# esquematico.net
KiCad netlist of a schematic drawn in Altium Designer
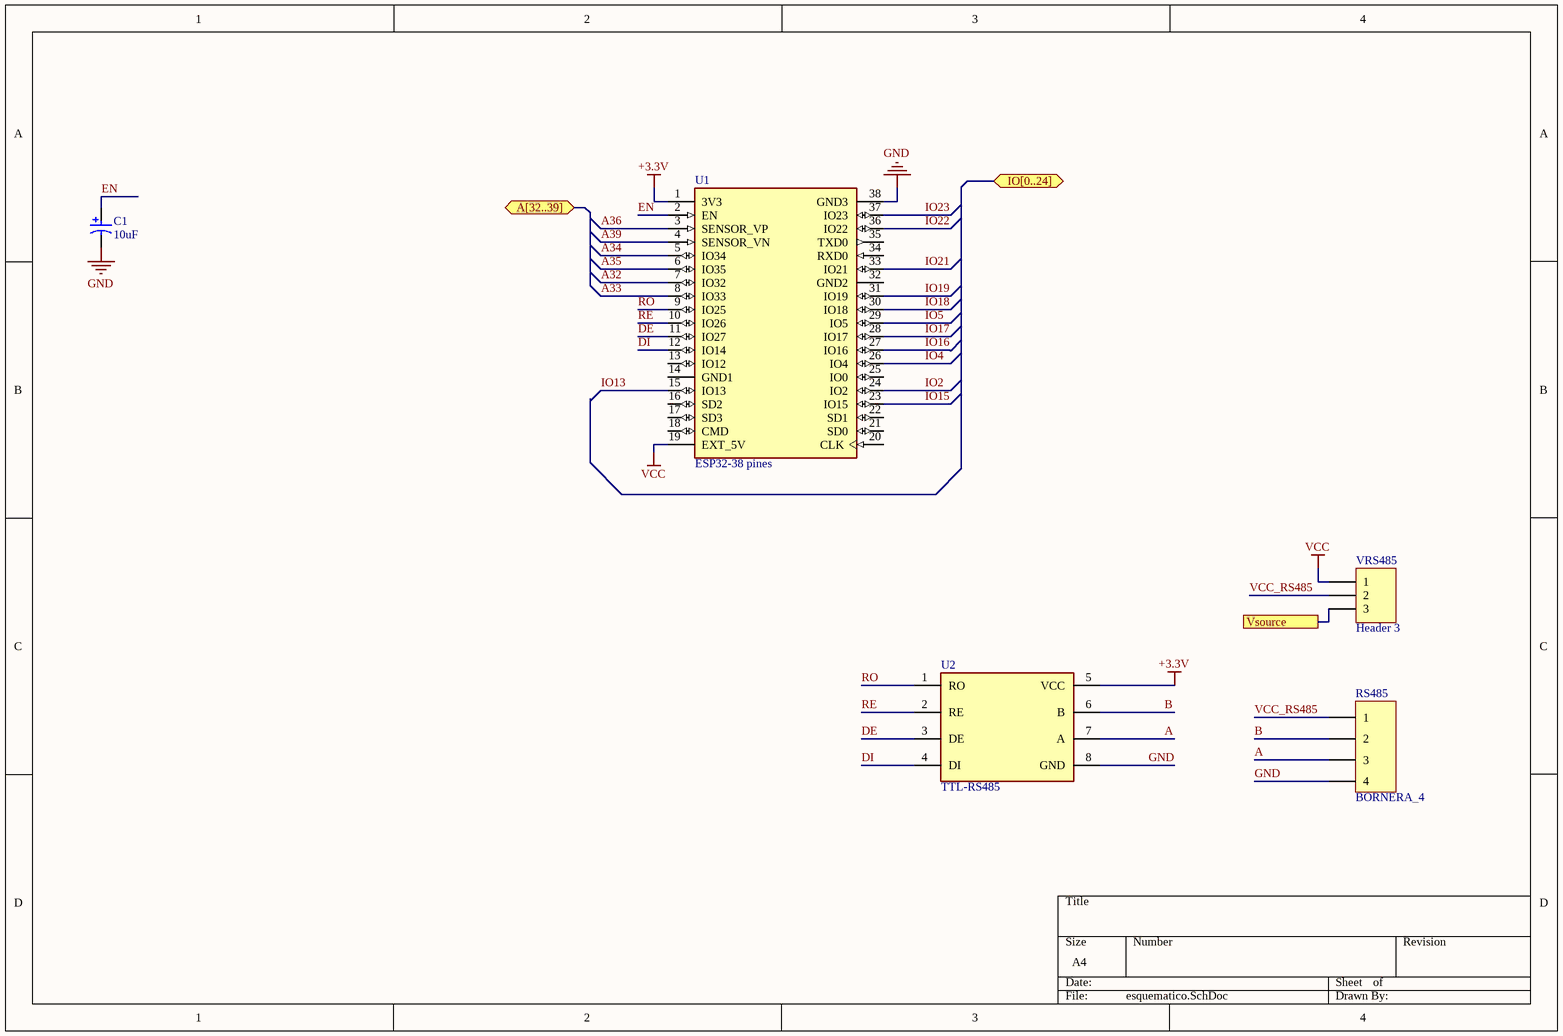
[diagram p0: esquematico.SchDoc]

(export (version "E")
  (design (tool "Eeschema 10.0.6"))
  (components
    (comp (ref "C1")
      (value "10uF")
      (footprint "FP-CAPACITOR")
      (libsource (lib "simbologia") (part "Electrolytic capacitor"))
    )
    (comp (ref "RS485")
      (value "BORNERA_4")
      (footprint "BORNERA_4")
      (libsource (lib "simbologia") (part "BORNERA_4"))
    )
    (comp (ref "U1")
      (value "ESP32-38 pines")
      (footprint "ESP32")
      (libsource (lib "simbologia") (part "ESP32-38 pines"))
    )
    (comp (ref "U2")
      (value "TTL-RS485")
      (footprint "TTL_RS485")
      (libsource (lib "simbologia") (part "TTL-RS485"))
    )
    (comp (ref "VRS485")
      (value "Header 3")
      (footprint "HDR1X3")
      (description "Header, 3-Pin")
      (fields (field (name "PUBLISHER") "Altium Limited"))
      (libsource (lib "Miscellaneous Connectors") (part "Header 3"))
    )
  )
  (nets
    (net (code "16") (name "+3.3V") (class "Default")
      (node (ref "U1") (pin "1") (pinfunction "3V3_1") (pintype "power_in"))
      (node (ref "U2") (pin "5") (pinfunction "VCC_5") (pintype "power_in"))
    )
    (net (code "17") (name "/A") (class "Default")
      (node (ref "RS485") (pin "3") (pinfunction "3_3") (pintype "passive"))
      (node (ref "U2") (pin "7") (pinfunction "A_7") (pintype "power_in"))
    )
    (net (code "18") (name "/A32") (class "Default")
      (node (ref "U1") (pin "7") (pinfunction "IO32_7") (pintype "bidirectional"))
    )
    (net (code "19") (name "/A33") (class "Default")
      (node (ref "U1") (pin "8") (pinfunction "IO33_8") (pintype "bidirectional"))
    )
    (net (code "20") (name "/A34") (class "Default")
      (node (ref "U1") (pin "5") (pinfunction "IO34_5") (pintype "bidirectional"))
    )
    (net (code "21") (name "/A35") (class "Default")
      (node (ref "U1") (pin "6") (pinfunction "IO35_6") (pintype "bidirectional"))
    )
    (net (code "22") (name "/A36") (class "Default")
      (node (ref "U1") (pin "3") (pinfunction "SENSOR_VP_3") (pintype "input"))
    )
    (net (code "23") (name "/A39") (class "Default")
      (node (ref "U1") (pin "4") (pinfunction "SENSOR_VN_4") (pintype "input"))
    )
    (net (code "25") (name "/B") (class "Default")
      (node (ref "RS485") (pin "2") (pinfunction "2_2") (pintype "passive"))
      (node (ref "U2") (pin "6") (pinfunction "B_6") (pintype "power_in"))
    )
    (net (code "26") (name "/DE") (class "Default")
      (node (ref "U1") (pin "11") (pinfunction "IO27_11") (pintype "bidirectional"))
      (node (ref "U2") (pin "3") (pinfunction "DE_3") (pintype "power_in"))
    )
    (net (code "27") (name "/DI") (class "Default")
      (node (ref "U1") (pin "12") (pinfunction "IO14_12") (pintype "bidirectional"))
      (node (ref "U2") (pin "4") (pinfunction "DI_4") (pintype "power_in"))
    )
    (net (code "28") (name "/EN") (class "Default")
      (node (ref "C1") (pin "1") (pinfunction "1_1") (pintype "passive"))
      (node (ref "U1") (pin "2") (pinfunction "EN_2") (pintype "input"))
    )
    (net (code "29") (name "/IO2") (class "Default")
      (node (ref "U1") (pin "24") (pinfunction "IO2_24") (pintype "bidirectional"))
    )
    (net (code "30") (name "/IO4") (class "Default")
      (node (ref "U1") (pin "26") (pinfunction "IO4_26") (pintype "bidirectional"))
    )
    (net (code "31") (name "/IO5") (class "Default")
      (node (ref "U1") (pin "29") (pinfunction "IO5_29") (pintype "bidirectional"))
    )
    (net (code "32") (name "/IO13") (class "Default")
      (node (ref "U1") (pin "15") (pinfunction "IO13_15") (pintype "bidirectional"))
    )
    (net (code "33") (name "/IO15") (class "Default")
      (node (ref "U1") (pin "23") (pinfunction "IO15_23") (pintype "bidirectional"))
    )
    (net (code "34") (name "/IO16") (class "Default")
      (node (ref "U1") (pin "27") (pinfunction "IO16_27") (pintype "bidirectional"))
    )
    (net (code "35") (name "/IO17") (class "Default")
      (node (ref "U1") (pin "28") (pinfunction "IO17_28") (pintype "bidirectional"))
    )
    (net (code "36") (name "/IO18") (class "Default")
      (node (ref "U1") (pin "30") (pinfunction "IO18_30") (pintype "bidirectional"))
    )
    (net (code "37") (name "/IO19") (class "Default")
      (node (ref "U1") (pin "31") (pinfunction "IO19_31") (pintype "bidirectional"))
    )
    (net (code "38") (name "/IO21") (class "Default")
      (node (ref "U1") (pin "33") (pinfunction "IO21_33") (pintype "bidirectional"))
    )
    (net (code "39") (name "/IO22") (class "Default")
      (node (ref "U1") (pin "36") (pinfunction "IO22_36") (pintype "bidirectional"))
    )
    (net (code "40") (name "/IO23") (class "Default")
      (node (ref "U1") (pin "37") (pinfunction "IO23_37") (pintype "bidirectional"))
    )
    (net (code "42") (name "/RE") (class "Default")
      (node (ref "U1") (pin "10") (pinfunction "IO26_10") (pintype "bidirectional"))
      (node (ref "U2") (pin "2") (pinfunction "RE_2") (pintype "power_in"))
    )
    (net (code "43") (name "/RO") (class "Default")
      (node (ref "U1") (pin "9") (pinfunction "IO25_9") (pintype "bidirectional"))
      (node (ref "U2") (pin "1") (pinfunction "RO_1") (pintype "power_in"))
    )
    (net (code "44") (name "/VCC_RS485") (class "Default")
      (node (ref "RS485") (pin "1") (pinfunction "1_1") (pintype "passive"))
      (node (ref "VRS485") (pin "2") (pinfunction "2_2") (pintype "passive"))
    )
    (net (code "45") (name "/Vsource") (class "Default")
      (node (ref "VRS485") (pin "3") (pinfunction "3_3") (pintype "passive"))
    )
    (net (code "46") (name "GND") (class "Default")
      (node (ref "C1") (pin "2") (pinfunction "2_2") (pintype "passive"))
      (node (ref "RS485") (pin "4") (pinfunction "4_4") (pintype "passive"))
      (node (ref "U1") (pin "38") (pinfunction "GND3_38") (pintype "power_in"))
      (node (ref "U2") (pin "8") (pinfunction "GND_8") (pintype "power_in"))
    )
    (net (code "47") (name "VCC") (class "Default")
      (node (ref "U1") (pin "19") (pinfunction "EXT_5V_19") (pintype "power_in"))
      (node (ref "VRS485") (pin "1") (pinfunction "1_1") (pintype "passive"))
    )
    (net (code "48") (name "unconnected-(U1-CLK-Pad20)") (class "Default")
      (node (ref "U1") (pin "20") (pinfunction "CLK_20") (pintype "input"))
    )
    (net (code "49") (name "unconnected-(U1-CMD-Pad18)") (class "Default")
      (node (ref "U1") (pin "18") (pinfunction "CMD_18") (pintype "bidirectional"))
    )
    (net (code "50") (name "unconnected-(U1-GND1-Pad14)") (class "Default")
      (node (ref "U1") (pin "14") (pinfunction "GND1_14") (pintype "power_in"))
    )
    (net (code "51") (name "unconnected-(U1-GND2-Pad32)") (class "Default")
      (node (ref "U1") (pin "32") (pinfunction "GND2_32") (pintype "power_in"))
    )
    (net (code "52") (name "unconnected-(U1-IO0-Pad25)") (class "Default")
      (node (ref "U1") (pin "25") (pinfunction "IO0_25") (pintype "bidirectional"))
    )
    (net (code "53") (name "unconnected-(U1-IO12-Pad13)") (class "Default")
      (node (ref "U1") (pin "13") (pinfunction "IO12_13") (pintype "bidirectional"))
    )
    (net (code "54") (name "unconnected-(U1-RXD0-Pad34)") (class "Default")
      (node (ref "U1") (pin "34") (pinfunction "RXD0_34") (pintype "input"))
    )
    (net (code "55") (name "unconnected-(U1-SD0-Pad21)") (class "Default")
      (node (ref "U1") (pin "21") (pinfunction "SD0_21") (pintype "bidirectional"))
    )
    (net (code "56") (name "unconnected-(U1-SD1-Pad22)") (class "Default")
      (node (ref "U1") (pin "22") (pinfunction "SD1_22") (pintype "bidirectional"))
    )
    (net (code "57") (name "unconnected-(U1-SD2-Pad16)") (class "Default")
      (node (ref "U1") (pin "16") (pinfunction "SD2_16") (pintype "bidirectional"))
    )
    (net (code "58") (name "unconnected-(U1-SD3-Pad17)") (class "Default")
      (node (ref "U1") (pin "17") (pinfunction "SD3_17") (pintype "bidirectional"))
    )
    (net (code "59") (name "unconnected-(U1-TXD0-Pad35)") (class "Default")
      (node (ref "U1") (pin "35") (pinfunction "TXD0_35") (pintype "output"))
    )
  )
)
